# rw-linear-17mm-mk-1_2_2.net
KiCad netlist of a schematic drawn in EAGLE
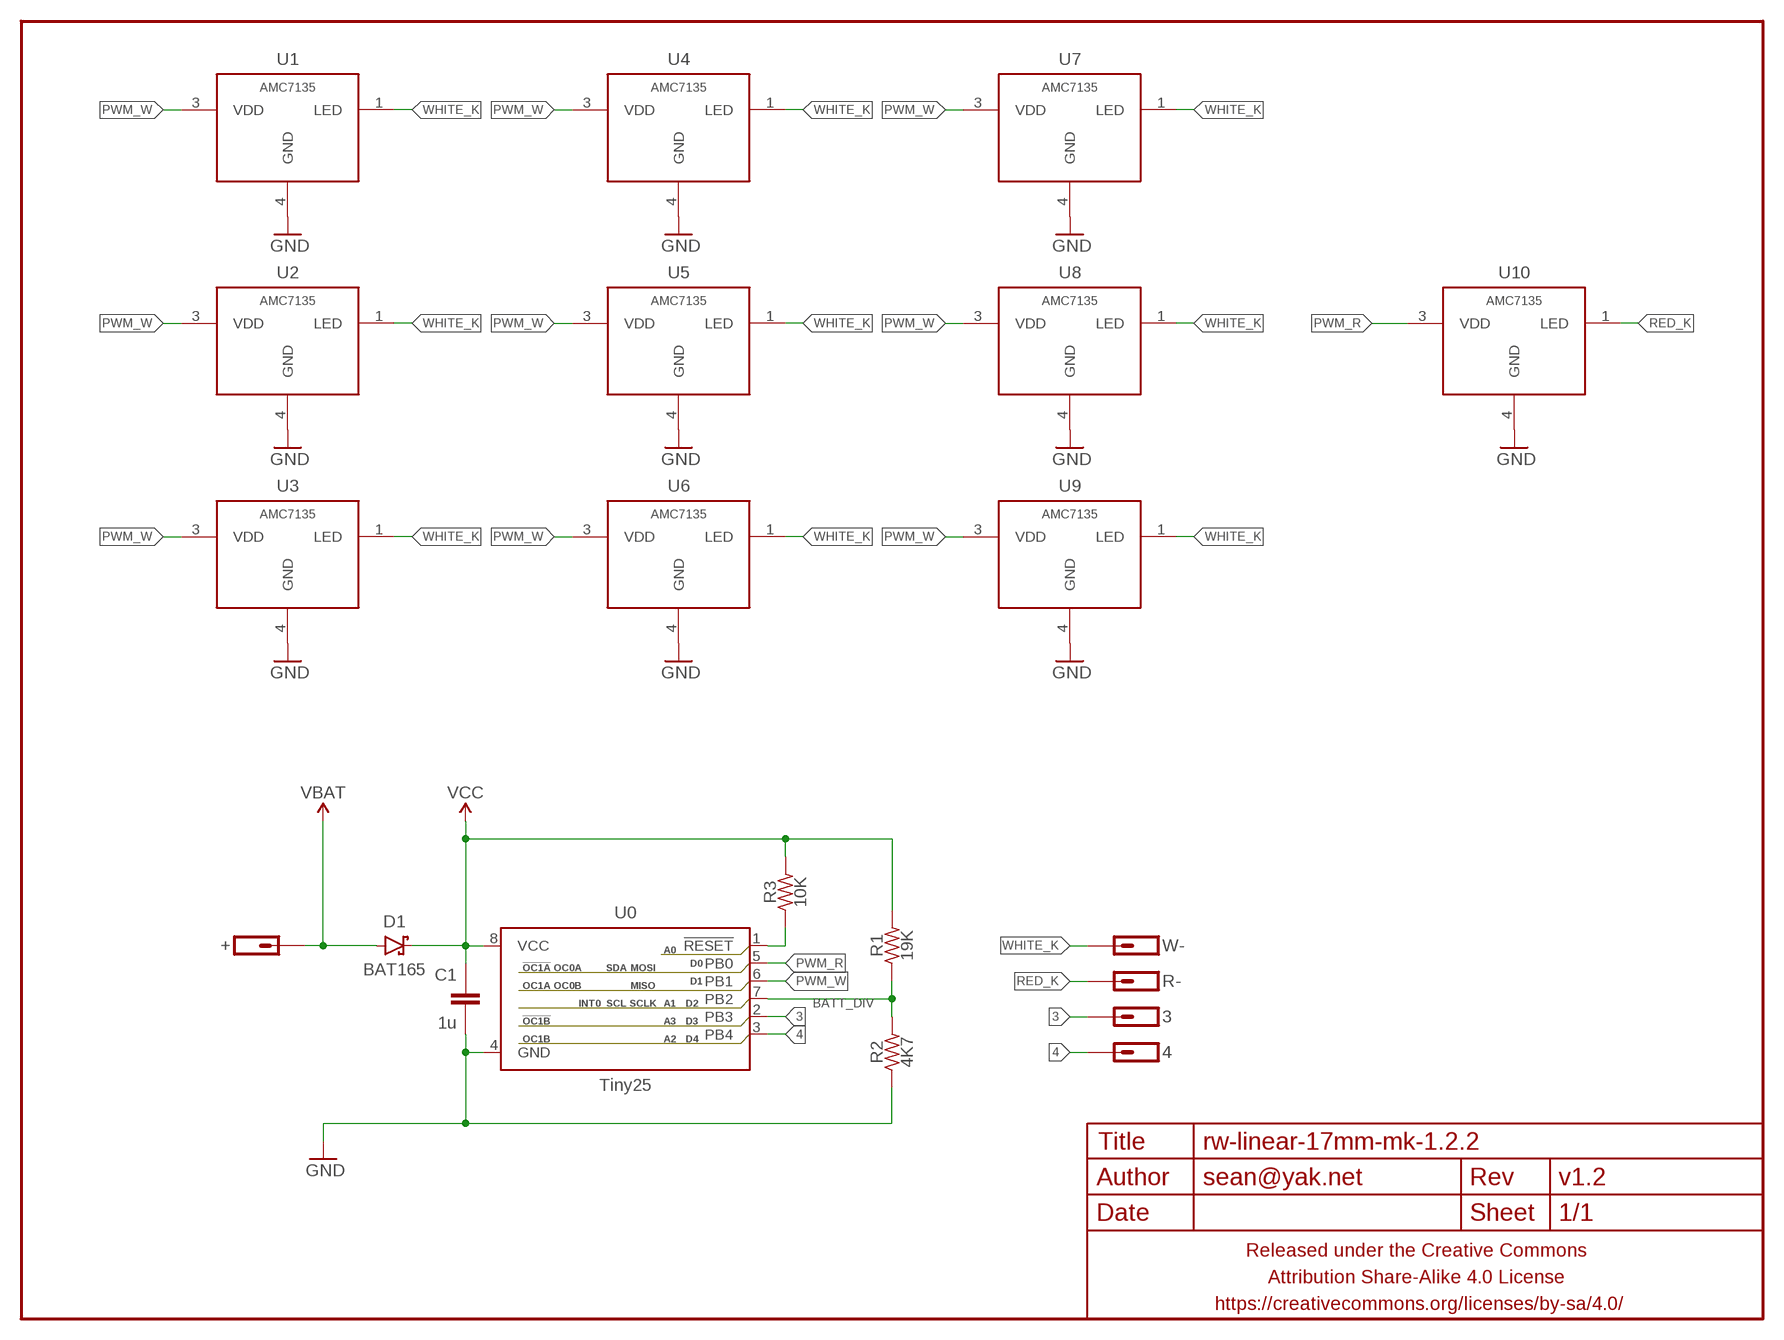
[diagram p0: schematic, sheet 1]

(export (version "E")
  (design (tool "Eeschema 10.0.6"))
  (components
    (comp (ref "+")
      (value "M01PTH-1.2MM-NS")
      (footprint "eagle-import:1X01-1.2MM-NS")
      (libsource (lib "eagle-import") (part "M01PTH-1.2MM-NS"))
    )
    (comp (ref "3")
      (value "M01SMD-1MM-DIA-NS")
      (footprint "eagle-import:1X01-SMD-1MM-DIA-NS")
      (libsource (lib "eagle-import") (part "M01SMD-1MM-DIA-NS"))
    )
    (comp (ref "4")
      (value "M01SMD-1MM-DIA-NS")
      (footprint "eagle-import:1X01-SMD-1MM-DIA-NS")
      (libsource (lib "eagle-import") (part "M01SMD-1MM-DIA-NS"))
    )
    (comp (ref "C1")
      (value "1u")
      (footprint "eagle-import:C0402")
      (libsource (lib "eagle-import") (part "CAPACITOR-CERAMICC0402"))
    )
    (comp (ref "D1")
      (value "BAT165")
      (footprint "eagle-import:SOD323-SCHOTTKY")
      (libsource (lib "eagle-import") (part "DIODE-SCHOTTKYSOD323"))
    )
    (comp (ref "FRAME1")
      (value "FRAME-LETTERNO_PACKAGE")
      (footprint "eagle-import:DUMMY")
      (fields (field (name "DESIGNER") "sean@yak.net") (field (name "VERSION") "v1.2"))
      (libsource (lib "eagle-import") (part "FRAME-LETTERNO_PACKAGE"))
    )
    (comp (ref "R-")
      (value "M01SMD-1.25MM-DIA")
      (footprint "eagle-import:1X01-SMD-1.25MM-DIA-NS")
      (libsource (lib "eagle-import") (part "M01SMD-1.25MM-DIA"))
    )
    (comp (ref "R1")
      (value "19K")
      (footprint "eagle-import:R0402")
      (libsource (lib "eagle-import") (part "RESISTORR0402"))
    )
    (comp (ref "R2")
      (value "4K7")
      (footprint "eagle-import:R0402")
      (libsource (lib "eagle-import") (part "RESISTORR0402"))
    )
    (comp (ref "R3")
      (value "10K")
      (footprint "eagle-import:R0402")
      (libsource (lib "eagle-import") (part "RESISTORR0402"))
    )
    (comp (ref "U0")
      (value "Tiny25")
      (footprint "eagle-import:SO08-NARROWER")
      (libsource (lib "eagle-import") (part "ATTINY13SOIC-NARROWPADS"))
    )
    (comp (ref "U1")
      (value "AMC7135")
      (footprint "eagle-import:SOT89-NOTHERM-ROUNDED-LESS")
      (libsource (lib "eagle-import") (part "AMC7135SOT-89-NOTHERM-ROUNDED-LESS"))
    )
    (comp (ref "U2")
      (value "AMC7135")
      (footprint "eagle-import:SOT89-NOTHERM-ROUNDED-LESS")
      (libsource (lib "eagle-import") (part "AMC7135SOT-89-NOTHERM-ROUNDED-LESS"))
    )
    (comp (ref "U3")
      (value "AMC7135")
      (footprint "eagle-import:SOT89-NOTHERM-ROUNDED-LESS")
      (libsource (lib "eagle-import") (part "AMC7135SOT-89-NOTHERM-ROUNDED-LESS"))
    )
    (comp (ref "U4")
      (value "AMC7135")
      (footprint "eagle-import:SOT89-NOTHERM-ROUNDED-LESS")
      (libsource (lib "eagle-import") (part "AMC7135SOT-89-NOTHERM-ROUNDED-LESS"))
    )
    (comp (ref "U5")
      (value "AMC7135")
      (footprint "eagle-import:SOT89-NOTHERM-ROUNDED-LESS")
      (libsource (lib "eagle-import") (part "AMC7135SOT-89-NOTHERM-ROUNDED-LESS"))
    )
    (comp (ref "U6")
      (value "AMC7135")
      (footprint "eagle-import:SOT89-NOTHERM-ROUNDED-LESS")
      (libsource (lib "eagle-import") (part "AMC7135SOT-89-NOTHERM-ROUNDED-LESS"))
    )
    (comp (ref "U7")
      (value "AMC7135")
      (footprint "eagle-import:SOT89-NOTHERM-ROUNDED-LESS")
      (libsource (lib "eagle-import") (part "AMC7135SOT-89-NOTHERM-ROUNDED-LESS"))
    )
    (comp (ref "U8")
      (value "AMC7135")
      (footprint "eagle-import:SOT89-NOTHERM-ROUNDED-LESS")
      (libsource (lib "eagle-import") (part "AMC7135SOT-89-NOTHERM-ROUNDED-LESS"))
    )
    (comp (ref "U9")
      (value "AMC7135")
      (footprint "eagle-import:SOT89-NOTHERM-ROUNDED-LESS")
      (libsource (lib "eagle-import") (part "AMC7135SOT-89-NOTHERM-ROUNDED-LESS"))
    )
    (comp (ref "U10")
      (value "AMC7135")
      (footprint "eagle-import:SOT89-NOTHERM-ROUNDED-LESS")
      (libsource (lib "eagle-import") (part "AMC7135SOT-89-NOTHERM-ROUNDED-LESS"))
    )
    (comp (ref "W-")
      (value "M01SMD-1.5MM-DIA-NS")
      (footprint "eagle-import:1X01-SMD-1.5MM-DIA-NS")
      (libsource (lib "eagle-import") (part "M01SMD-1.5MM-DIA-NS"))
    )
  )
  (nets
    (net (code "1") (name "/BATT_DIV") (class "Default")
      (node (ref "R1") (pin "1") (pinfunction "1_1") (pintype "passive"))
      (node (ref "R2") (pin "2") (pinfunction "2_2") (pintype "passive"))
      (node (ref "U0") (pin "7") (pinfunction "PB2_7") (pintype "bidirectional"))
    )
    (net (code "2") (name "3") (class "Default")
      (node (ref "3") (pin "P$1") (pinfunction "1_P$1") (pintype "passive"))
      (node (ref "U0") (pin "2") (pinfunction "PB3_2") (pintype "bidirectional"))
    )
    (net (code "3") (name "4") (class "Default")
      (node (ref "4") (pin "P$1") (pinfunction "1_P$1") (pintype "passive"))
      (node (ref "U0") (pin "3") (pinfunction "PB4_3") (pintype "bidirectional"))
    )
    (net (code "4") (name "GND") (class "Default")
      (node (ref "C1") (pin "2") (pinfunction "2_2") (pintype "passive"))
      (node (ref "R2") (pin "1") (pinfunction "1_1") (pintype "passive"))
      (node (ref "U0") (pin "4") (pinfunction "GND_4") (pintype "bidirectional"))
      (node (ref "U1") (pin "4") (pinfunction "GND_4") (pintype "bidirectional"))
      (node (ref "U10") (pin "4") (pinfunction "GND_4") (pintype "bidirectional"))
      (node (ref "U2") (pin "4") (pinfunction "GND_4") (pintype "bidirectional"))
      (node (ref "U3") (pin "4") (pinfunction "GND_4") (pintype "bidirectional"))
      (node (ref "U4") (pin "4") (pinfunction "GND_4") (pintype "bidirectional"))
      (node (ref "U5") (pin "4") (pinfunction "GND_4") (pintype "bidirectional"))
      (node (ref "U6") (pin "4") (pinfunction "GND_4") (pintype "bidirectional"))
      (node (ref "U7") (pin "4") (pinfunction "GND_4") (pintype "bidirectional"))
      (node (ref "U8") (pin "4") (pinfunction "GND_4") (pintype "bidirectional"))
      (node (ref "U9") (pin "4") (pinfunction "GND_4") (pintype "bidirectional"))
    )
    (net (code "5") (name "Net-(U0-~{RESET})") (class "Default")
      (node (ref "R3") (pin "1") (pinfunction "1_1") (pintype "passive"))
      (node (ref "U0") (pin "1") (pinfunction "~{RESET}_1") (pintype "bidirectional"))
    )
    (net (code "6") (name "PWM_R") (class "Default")
      (node (ref "U0") (pin "5") (pinfunction "PB0_5") (pintype "bidirectional"))
      (node (ref "U10") (pin "3") (pinfunction "VDD_3") (pintype "bidirectional"))
    )
    (net (code "7") (name "PWM_W") (class "Default")
      (node (ref "U0") (pin "6") (pinfunction "PB1_6") (pintype "bidirectional"))
      (node (ref "U1") (pin "3") (pinfunction "VDD_3") (pintype "bidirectional"))
      (node (ref "U2") (pin "3") (pinfunction "VDD_3") (pintype "bidirectional"))
      (node (ref "U3") (pin "3") (pinfunction "VDD_3") (pintype "bidirectional"))
      (node (ref "U4") (pin "3") (pinfunction "VDD_3") (pintype "bidirectional"))
      (node (ref "U5") (pin "3") (pinfunction "VDD_3") (pintype "bidirectional"))
      (node (ref "U6") (pin "3") (pinfunction "VDD_3") (pintype "bidirectional"))
      (node (ref "U7") (pin "3") (pinfunction "VDD_3") (pintype "bidirectional"))
      (node (ref "U8") (pin "3") (pinfunction "VDD_3") (pintype "bidirectional"))
      (node (ref "U9") (pin "3") (pinfunction "VDD_3") (pintype "bidirectional"))
    )
    (net (code "8") (name "RED_K") (class "Default")
      (node (ref "R-") (pin "P$1") (pinfunction "1_P$1") (pintype "passive"))
      (node (ref "U10") (pin "1") (pinfunction "LED_1") (pintype "bidirectional"))
    )
    (net (code "9") (name "VBAT") (class "Default")
      (node (ref "+") (pin "P$1") (pinfunction "1_P$1") (pintype "passive"))
      (node (ref "D1") (pin "A") (pinfunction "A_A") (pintype "passive"))
    )
    (net (code "10") (name "VCC") (class "Default")
      (node (ref "C1") (pin "1") (pinfunction "1_1") (pintype "passive"))
      (node (ref "D1") (pin "C") (pinfunction "C_C") (pintype "passive"))
      (node (ref "R1") (pin "2") (pinfunction "2_2") (pintype "passive"))
      (node (ref "R3") (pin "2") (pinfunction "2_2") (pintype "passive"))
      (node (ref "U0") (pin "8") (pinfunction "VCC_8") (pintype "bidirectional"))
    )
    (net (code "11") (name "WHITE_K") (class "Default")
      (node (ref "U1") (pin "1") (pinfunction "LED_1") (pintype "bidirectional"))
      (node (ref "U2") (pin "1") (pinfunction "LED_1") (pintype "bidirectional"))
      (node (ref "U3") (pin "1") (pinfunction "LED_1") (pintype "bidirectional"))
      (node (ref "U4") (pin "1") (pinfunction "LED_1") (pintype "bidirectional"))
      (node (ref "U5") (pin "1") (pinfunction "LED_1") (pintype "bidirectional"))
      (node (ref "U6") (pin "1") (pinfunction "LED_1") (pintype "bidirectional"))
      (node (ref "U7") (pin "1") (pinfunction "LED_1") (pintype "bidirectional"))
      (node (ref "U8") (pin "1") (pinfunction "LED_1") (pintype "bidirectional"))
      (node (ref "U9") (pin "1") (pinfunction "LED_1") (pintype "bidirectional"))
      (node (ref "W-") (pin "P$1") (pinfunction "1_P$1") (pintype "passive"))
    )
  )
)
